# TML_Tick_Tacho_Timergrapher_Mic.net
KiCad netlist of a schematic drawn in EAGLE
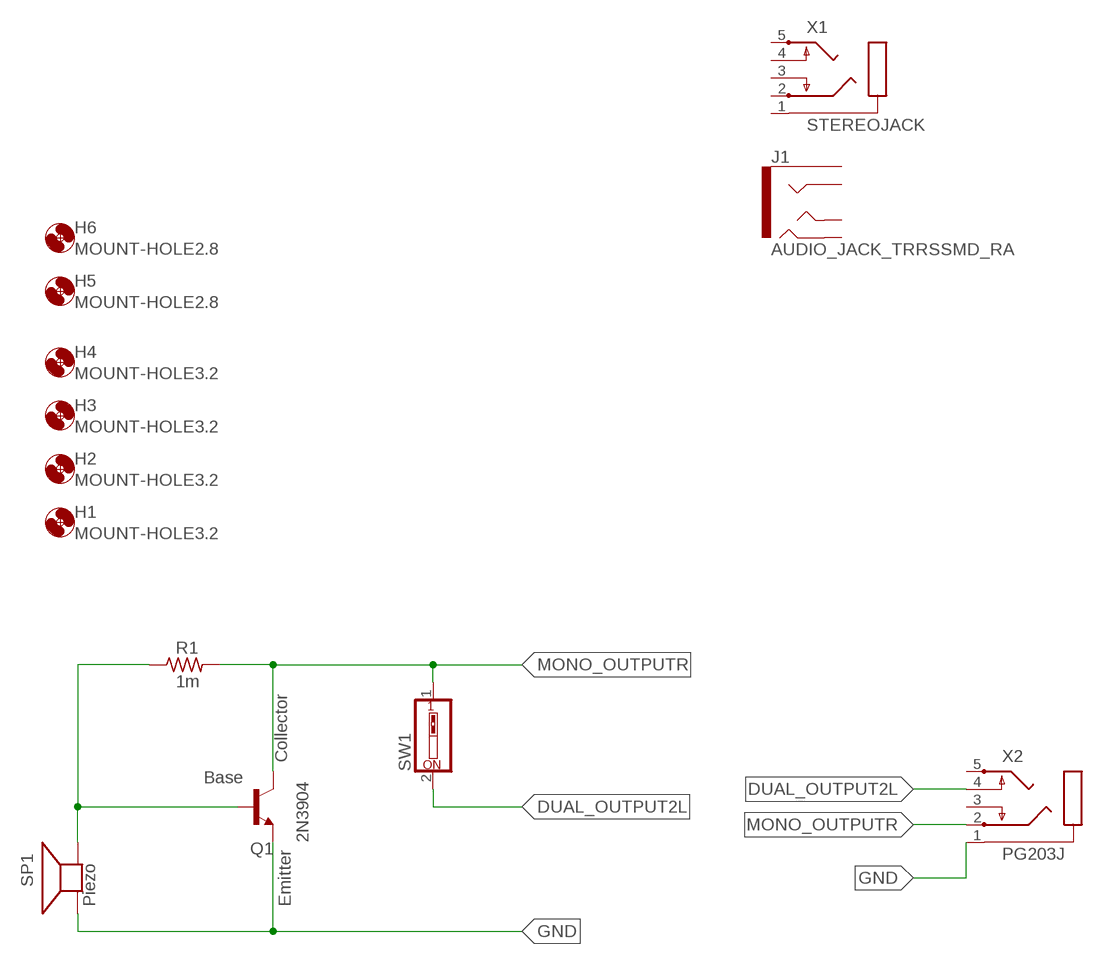
[diagram p0: schematic, sheet 1]

(export (version "E")
  (design (tool "Eeschema 10.0.6"))
  (components
    (comp (ref "H1")
      (value "MOUNT-HOLE3.2")
      (footprint "eagle-import:3,2")
      (libsource (lib "eagle-import") (part "MOUNT-HOLE3.2"))
    )
    (comp (ref "H2")
      (value "MOUNT-HOLE3.2")
      (footprint "eagle-import:3,2")
      (libsource (lib "eagle-import") (part "MOUNT-HOLE3.2"))
    )
    (comp (ref "H3")
      (value "MOUNT-HOLE3.2")
      (footprint "eagle-import:3,2")
      (libsource (lib "eagle-import") (part "MOUNT-HOLE3.2"))
    )
    (comp (ref "H4")
      (value "MOUNT-HOLE3.2")
      (footprint "eagle-import:3,2")
      (libsource (lib "eagle-import") (part "MOUNT-HOLE3.2"))
    )
    (comp (ref "H5")
      (value "MOUNT-HOLE2.8")
      (footprint "eagle-import:2,8")
      (libsource (lib "eagle-import") (part "MOUNT-HOLE2.8"))
    )
    (comp (ref "H6")
      (value "MOUNT-HOLE2.8")
      (footprint "eagle-import:2,8")
      (libsource (lib "eagle-import") (part "MOUNT-HOLE2.8"))
    )
    (comp (ref "J1")
      (value "AUDIO_JACK_TRRSSMD_RA")
      (footprint "eagle-import:AUDIO_JACK_3.5MM_TRRS_SMD_RA")
      (libsource (lib "eagle-import") (part "AUDIO_JACK_TRRSSMD_RA"))
    )
    (comp (ref "Q1")
      (value "2N3904")
      (footprint "eagle-import:TO92")
      (libsource (lib "eagle-import") (part "2N3904"))
    )
    (comp (ref "R1")
      (value "1m")
      (footprint "eagle-import:0204_7")
      (libsource (lib "eagle-import") (part "R-US_0204/7"))
    )
    (comp (ref "SP1")
      (value "Piezo")
      (footprint "eagle-import:AL60P")
      (libsource (lib "eagle-import") (part "SPEAKER/AL60P"))
    )
    (comp (ref "SW1")
      (value "SW_DIP-1")
      (footprint "eagle-import:EDG-01")
      (libsource (lib "eagle-import") (part "SW_DIP-1"))
    )
    (comp (ref "X1")
      (value "STEREOJACK")
      (footprint "eagle-import:STX3100")
      (libsource (lib "eagle-import") (part "STEREOJACK"))
    )
    (comp (ref "X2")
      (value "PG203J")
      (footprint "eagle-import:PG203J")
      (libsource (lib "eagle-import") (part "PG203J"))
    )
  )
  (nets
    (net (code "1") (name "DUAL_OUTPUT2L") (class "Default")
      (node (ref "SW1") (pin "2") (pinfunction "2_2") (pintype "passive"))
      (node (ref "X2") (pin "4") (pinfunction "4_4") (pintype "passive"))
    )
    (net (code "2") (name "GND") (class "Default")
      (node (ref "Q1") (pin "3") (pinfunction "E_3") (pintype "passive"))
      (node (ref "SP1") (pin "1") (pinfunction "+_1") (pintype "passive"))
      (node (ref "X2") (pin "1") (pinfunction "1_1") (pintype "passive"))
    )
    (net (code "3") (name "MONO_OUTPUTR") (class "Default")
      (node (ref "Q1") (pin "1") (pinfunction "C_1") (pintype "passive"))
      (node (ref "R1") (pin "2") (pinfunction "2_2") (pintype "passive"))
      (node (ref "SW1") (pin "1") (pinfunction "1_1") (pintype "passive"))
      (node (ref "X2") (pin "2") (pinfunction "2_2") (pintype "passive"))
    )
    (net (code "4") (name "Net-(Q1-B)") (class "Default")
      (node (ref "Q1") (pin "2") (pinfunction "B_2") (pintype "passive"))
      (node (ref "R1") (pin "1") (pinfunction "1_1") (pintype "passive"))
      (node (ref "SP1") (pin "2") (pinfunction "-_2") (pintype "passive"))
    )
    (net (code "5") (name "unconnected-(J1-PadEARTH)") (class "Default")
      (node (ref "J1") (pin "EARTH") (pinfunction "EARTH_EARTH") (pintype "bidirectional"))
    )
    (net (code "6") (name "unconnected-(J1-PadRING1)") (class "Default")
      (node (ref "J1") (pin "RING1") (pinfunction "RING1_RING1") (pintype "bidirectional"))
    )
    (net (code "7") (name "unconnected-(J1-PadRING2)") (class "Default")
      (node (ref "J1") (pin "RING2") (pinfunction "RING2_RING2") (pintype "bidirectional"))
    )
    (net (code "8") (name "unconnected-(J1-PadTIP)") (class "Default")
      (node (ref "J1") (pin "TIP") (pinfunction "TIP_TIP") (pintype "bidirectional"))
    )
    (net (code "9") (name "unconnected-(X1-Pad1)") (class "Default")
      (node (ref "X1") (pin "1") (pinfunction "1_1") (pintype "passive"))
    )
    (net (code "10") (name "unconnected-(X1-Pad2)") (class "Default")
      (node (ref "X1") (pin "2") (pinfunction "2_2") (pintype "passive"))
    )
    (net (code "11") (name "unconnected-(X1-Pad3)") (class "Default")
      (node (ref "X1") (pin "3") (pinfunction "3_3") (pintype "passive"))
    )
    (net (code "12") (name "unconnected-(X1-Pad4)") (class "Default")
      (node (ref "X1") (pin "4") (pinfunction "4_4") (pintype "passive"))
    )
    (net (code "13") (name "unconnected-(X1-Pad5)") (class "Default")
      (node (ref "X1") (pin "5") (pinfunction "5_5") (pintype "passive"))
    )
    (net (code "14") (name "unconnected-(X2-Pad3)") (class "Default")
      (node (ref "X2") (pin "3") (pinfunction "3_3") (pintype "passive"))
    )
    (net (code "15") (name "unconnected-(X2-Pad5)") (class "Default")
      (node (ref "X2") (pin "5") (pinfunction "5_5") (pintype "passive"))
    )
  )
)
